# ESP_Breakout.net
KiCad netlist of a schematic drawn in EAGLE
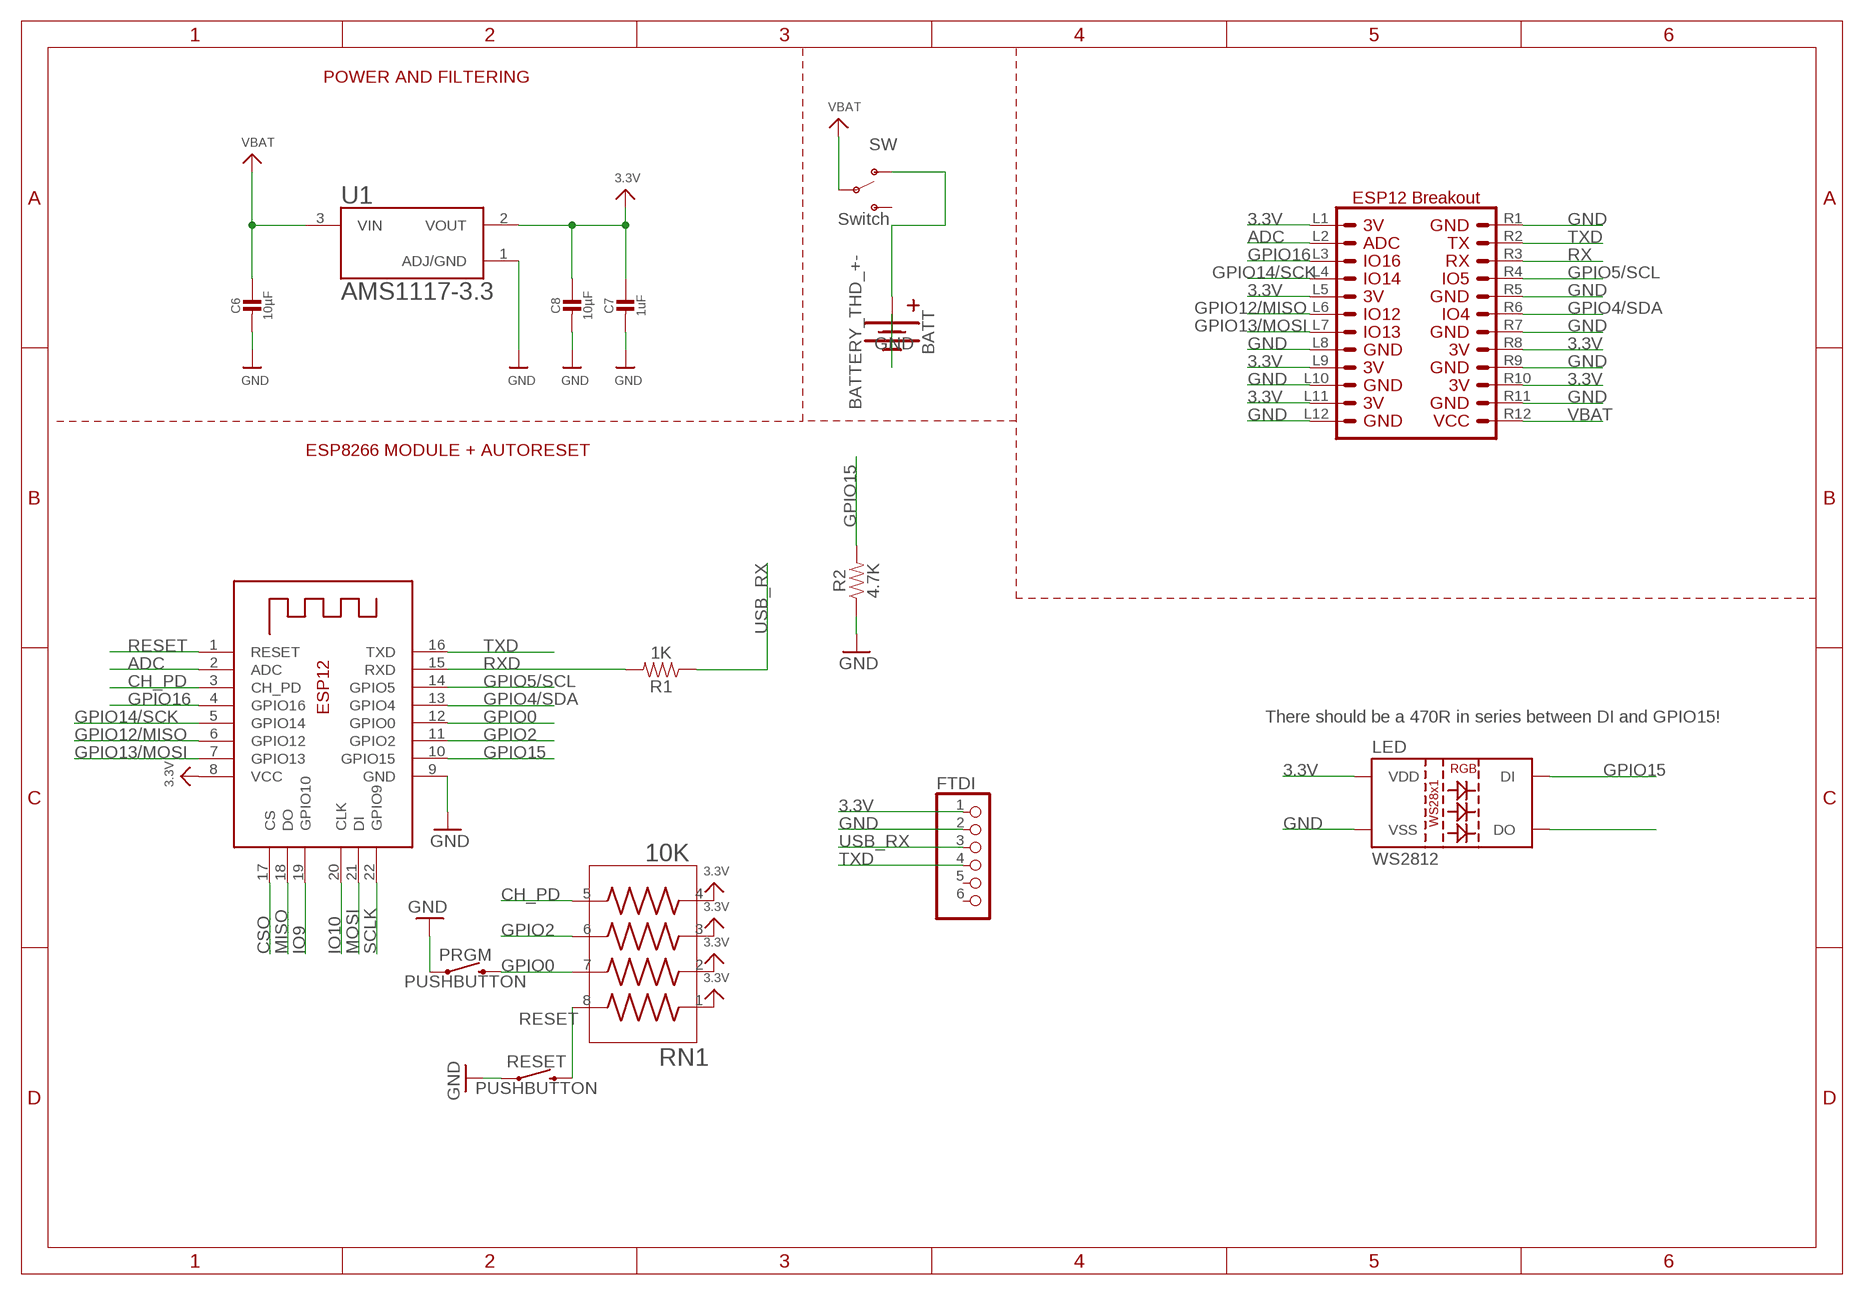
[diagram p0: schematic, sheet 1]

(export (version "E")
  (design (tool "Eeschema 10.0.6"))
  (components
    (comp (ref "BATT")
      (value "BATTERY_THD_+-")
      (footprint "eagle-import:1X02_PLUS_MINUS")
      (libsource (lib "eagle-import") (part "BATTERY_THD_+-"))
    )
    (comp (ref "C6")
      (value "10µF")
      (footprint "eagle-import:MICROBUILDER__0805")
      (libsource (lib "eagle-import") (part "MICROBUILDER_CAP_CERAMIC_0805"))
    )
    (comp (ref "C7")
      (value "1uF")
      (footprint "eagle-import:MICROBUILDER__0603")
      (libsource (lib "eagle-import") (part "MICROBUILDER_CAP_CERAMIC_0603"))
    )
    (comp (ref "C8")
      (value "10µF")
      (footprint "eagle-import:MICROBUILDER__0805")
      (libsource (lib "eagle-import") (part "MICROBUILDER_CAP_CERAMIC_0805"))
    )
    (comp (ref "FTDI")
      (value "PINHD-1X6")
      (footprint "eagle-import:1X06")
      (libsource (lib "eagle-import") (part "PINHD-1X6"))
    )
    (comp (ref "LED")
      (value "WS2812")
      (footprint "eagle-import:LED-TRICOLOR-5050-IC")
      (libsource (lib "eagle-import") (part "WS2812"))
    )
    (comp (ref "PRGM")
      (value "PUSHBUTTON")
      (footprint "eagle-import:TACTILE_SWITCH_SMD_6.0X3.5MM")
      (libsource (lib "eagle-import") (part "PUSHBUTTON"))
    )
    (comp (ref "R1")
      (value "1K")
      (footprint "eagle-import:1206")
      (libsource (lib "eagle-import") (part "RESISTOR1206"))
    )
    (comp (ref "R2")
      (value "4.7K")
      (footprint "eagle-import:1206")
      (libsource (lib "eagle-import") (part "RESISTOR1206"))
    )
    (comp (ref "RESET")
      (value "PUSHBUTTON")
      (footprint "eagle-import:TACTILE_SWITCH_SMD_6.0X3.5MM")
      (libsource (lib "eagle-import") (part "PUSHBUTTON"))
    )
    (comp (ref "RN1")
      (value "10K")
      (footprint "eagle-import:RESCAF80P320X160X60-8N")
      (fields (field (name "MF") "Bourns") (field (name "MP") "CAY16-750J4LF"))
      (libsource (lib "eagle-import") (part "RESISTOR_ARRAY_1206"))
    )
    (comp (ref "SW")
      (value "Switch")
      (footprint "eagle-import:SWITCH_SPDT_PTH_11.6X4.0MM")
      (libsource (lib "eagle-import") (part "SWITCH_SPDT_SLIDE"))
    )
    (comp (ref "U$7")
      (value "ESP12_BREAKOUT")
      (footprint "eagle-import:ESP12_BREAKOUT_CONN")
      (libsource (lib "eagle-import") (part "ESP12_BREAKOUT"))
    )
    (comp (ref "U1")
      (value "AMS1117-3.3")
      (footprint "eagle-import:SOT229P700X180-4N")
      (fields (field (name "MF") "Advanced Monolithic Systems"))
      (libsource (lib "eagle-import") (part "AMS1117-3.3"))
    )
    (comp (ref "X2")
      (value "ESP-12")
      (footprint "eagle-import:ESP-12E")
      (libsource (lib "eagle-import") (part "ESP-12E"))
    )
  )
  (nets
    (net (code "1") (name "/ADC") (class "Default")
      (node (ref "U$7") (pin "L2") (pinfunction "L2_L2") (pintype "passive"))
      (node (ref "X2") (pin "2") (pinfunction "ADC_2") (pintype "passive"))
    )
    (net (code "2") (name "/CH_PD") (class "Default")
      (node (ref "RN1") (pin "5") (pinfunction "5_5") (pintype "passive"))
      (node (ref "X2") (pin "3") (pinfunction "CH_PD_3") (pintype "input"))
    )
    (net (code "3") (name "/CSO") (class "Default")
      (node (ref "X2") (pin "17") (pinfunction "CS_17") (pintype "bidirectional"))
    )
    (net (code "4") (name "/GPIO0") (class "Default")
      (node (ref "PRGM") (pin "2") (pinfunction "2_2") (pintype "passive"))
      (node (ref "RN1") (pin "7") (pinfunction "7_7") (pintype "passive"))
      (node (ref "X2") (pin "12") (pinfunction "GPIO0_12") (pintype "bidirectional"))
    )
    (net (code "5") (name "/GPIO2") (class "Default")
      (node (ref "RN1") (pin "6") (pinfunction "6_6") (pintype "passive"))
      (node (ref "X2") (pin "11") (pinfunction "GPIO2_11") (pintype "bidirectional"))
    )
    (net (code "6") (name "/GPIO4{slash}SDA") (class "Default")
      (node (ref "U$7") (pin "R6") (pinfunction "R6_R6") (pintype "passive"))
      (node (ref "X2") (pin "13") (pinfunction "GPIO4_13") (pintype "bidirectional"))
    )
    (net (code "7") (name "/GPIO5{slash}SCL") (class "Default")
      (node (ref "U$7") (pin "R4") (pinfunction "R4_R4") (pintype "passive"))
      (node (ref "X2") (pin "14") (pinfunction "GPIO5_14") (pintype "bidirectional"))
    )
    (net (code "8") (name "/GPIO12{slash}MISO") (class "Default")
      (node (ref "U$7") (pin "L6") (pinfunction "L6_L6") (pintype "passive"))
      (node (ref "X2") (pin "6") (pinfunction "GPIO12_6") (pintype "bidirectional"))
    )
    (net (code "9") (name "/GPIO13{slash}MOSI") (class "Default")
      (node (ref "U$7") (pin "L7") (pinfunction "L7_L7") (pintype "passive"))
      (node (ref "X2") (pin "7") (pinfunction "GPIO13_7") (pintype "bidirectional"))
    )
    (net (code "10") (name "/GPIO14{slash}SCK") (class "Default")
      (node (ref "U$7") (pin "L4") (pinfunction "L4_L4") (pintype "passive"))
      (node (ref "X2") (pin "5") (pinfunction "GPIO14_5") (pintype "bidirectional"))
    )
    (net (code "11") (name "/GPIO15") (class "Default")
      (node (ref "LED") (pin "DIN") (pinfunction "DI_DIN") (pintype "bidirectional"))
      (node (ref "R2") (pin "2") (pinfunction "2_2") (pintype "passive"))
      (node (ref "X2") (pin "10") (pinfunction "GPIO15_10") (pintype "bidirectional"))
    )
    (net (code "12") (name "/GPIO16") (class "Default")
      (node (ref "U$7") (pin "L3") (pinfunction "L3_L3") (pintype "passive"))
      (node (ref "X2") (pin "4") (pinfunction "GPIO16_4") (pintype "bidirectional"))
    )
    (net (code "13") (name "/IO9") (class "Default")
      (node (ref "X2") (pin "19") (pinfunction "GPIO10_19") (pintype "bidirectional"))
    )
    (net (code "14") (name "/IO10") (class "Default")
      (node (ref "X2") (pin "20") (pinfunction "CLK_20") (pintype "bidirectional"))
    )
    (net (code "15") (name "/MISO") (class "Default")
      (node (ref "X2") (pin "18") (pinfunction "DO_18") (pintype "bidirectional"))
    )
    (net (code "16") (name "/MOSI") (class "Default")
      (node (ref "X2") (pin "21") (pinfunction "DI_21") (pintype "bidirectional"))
    )
    (net (code "17") (name "/RESET") (class "Default")
      (node (ref "RESET") (pin "2") (pinfunction "2_2") (pintype "passive"))
      (node (ref "RN1") (pin "8") (pinfunction "8_8") (pintype "passive"))
      (node (ref "X2") (pin "1") (pinfunction "RESET_1") (pintype "input"))
    )
    (net (code "18") (name "/RX") (class "Default")
      (node (ref "U$7") (pin "R3") (pinfunction "R3_R3") (pintype "passive"))
    )
    (net (code "19") (name "/RXD") (class "Default")
      (node (ref "R1") (pin "2") (pinfunction "2_2") (pintype "passive"))
      (node (ref "X2") (pin "15") (pinfunction "RXD_15") (pintype "input"))
    )
    (net (code "20") (name "/SCLK") (class "Default")
      (node (ref "X2") (pin "22") (pinfunction "GPIO9_22") (pintype "bidirectional"))
    )
    (net (code "21") (name "/TXD") (class "Default")
      (node (ref "FTDI") (pin "4") (pinfunction "4_4") (pintype "passive"))
      (node (ref "U$7") (pin "R2") (pinfunction "R2_R2") (pintype "passive"))
      (node (ref "X2") (pin "16") (pinfunction "TXD_16") (pintype "output"))
    )
    (net (code "22") (name "/USB_RX") (class "Default")
      (node (ref "FTDI") (pin "3") (pinfunction "3_3") (pintype "passive"))
      (node (ref "R1") (pin "1") (pinfunction "1_1") (pintype "passive"))
    )
    (net (code "23") (name "3.3V") (class "Default")
      (node (ref "C7") (pin "1") (pinfunction "1_1") (pintype "passive"))
      (node (ref "C8") (pin "1") (pinfunction "1_1") (pintype "passive"))
      (node (ref "FTDI") (pin "1") (pinfunction "1_1") (pintype "passive"))
      (node (ref "LED") (pin "VDD") (pinfunction "VDD_VDD") (pintype "bidirectional"))
      (node (ref "RN1") (pin "1") (pinfunction "1_1") (pintype "passive"))
      (node (ref "RN1") (pin "2") (pinfunction "2_2") (pintype "passive"))
      (node (ref "RN1") (pin "3") (pinfunction "3_3") (pintype "passive"))
      (node (ref "RN1") (pin "4") (pinfunction "4_4") (pintype "passive"))
      (node (ref "U$7") (pin "L1") (pinfunction "L1_L1") (pintype "passive"))
      (node (ref "U$7") (pin "L11") (pinfunction "L11_L11") (pintype "passive"))
      (node (ref "U$7") (pin "L5") (pinfunction "L5_L5") (pintype "passive"))
      (node (ref "U$7") (pin "L9") (pinfunction "L9_L9") (pintype "passive"))
      (node (ref "U$7") (pin "R10") (pinfunction "R10_R10") (pintype "passive"))
      (node (ref "U$7") (pin "R8") (pinfunction "R8_R8") (pintype "passive"))
      (node (ref "U1") (pin "2") (pinfunction "VOUT_2") (pintype "output"))
      (node (ref "X2") (pin "8") (pinfunction "VCC_8") (pintype "power_in"))
    )
    (net (code "24") (name "GND") (class "Default")
      (node (ref "BATT") (pin "-") (pinfunction "-_-") (pintype "power_in"))
      (node (ref "C6") (pin "2") (pinfunction "2_2") (pintype "passive"))
      (node (ref "C7") (pin "2") (pinfunction "2_2") (pintype "passive"))
      (node (ref "C8") (pin "2") (pinfunction "2_2") (pintype "passive"))
      (node (ref "FTDI") (pin "2") (pinfunction "2_2") (pintype "passive"))
      (node (ref "LED") (pin "VSS") (pinfunction "VSS_VSS") (pintype "bidirectional"))
      (node (ref "PRGM") (pin "1") (pinfunction "1_1") (pintype "passive"))
      (node (ref "R2") (pin "1") (pinfunction "1_1") (pintype "passive"))
      (node (ref "RESET") (pin "1") (pinfunction "1_1") (pintype "passive"))
      (node (ref "U$7") (pin "L10") (pinfunction "L10_L10") (pintype "passive"))
      (node (ref "U$7") (pin "L12") (pinfunction "L12_L12") (pintype "passive"))
      (node (ref "U$7") (pin "L8") (pinfunction "L8_L8") (pintype "passive"))
      (node (ref "U$7") (pin "R1") (pinfunction "R1_R1") (pintype "passive"))
      (node (ref "U$7") (pin "R11") (pinfunction "R11_R11") (pintype "passive"))
      (node (ref "U$7") (pin "R5") (pinfunction "R5_R5") (pintype "passive"))
      (node (ref "U$7") (pin "R7") (pinfunction "R7_R7") (pintype "passive"))
      (node (ref "U$7") (pin "R9") (pinfunction "R9_R9") (pintype "passive"))
      (node (ref "U1") (pin "1") (pinfunction "ADJ/GND_1") (pintype "power_in"))
      (node (ref "X2") (pin "9") (pinfunction "GND_9") (pintype "power_in"))
    )
    (net (code "25") (name "Net-(SW-O)") (class "Default")
      (node (ref "BATT") (pin "+") (pinfunction "+_+") (pintype "power_in"))
      (node (ref "SW") (pin "1") (pinfunction "O_1") (pintype "passive"))
    )
    (net (code "26") (name "VBAT") (class "Default")
      (node (ref "C6") (pin "1") (pinfunction "1_1") (pintype "passive"))
      (node (ref "SW") (pin "2") (pinfunction "P_2") (pintype "passive"))
      (node (ref "U$7") (pin "R12") (pinfunction "R12_R12") (pintype "passive"))
      (node (ref "U1") (pin "3") (pinfunction "VIN_3") (pintype "input"))
    )
    (net (code "27") (name "unconnected-(FTDI-Pad5)") (class "Default")
      (node (ref "FTDI") (pin "5") (pinfunction "5_5") (pintype "passive"))
    )
    (net (code "28") (name "unconnected-(FTDI-Pad6)") (class "Default")
      (node (ref "FTDI") (pin "6") (pinfunction "6_6") (pintype "passive"))
    )
    (net (code "29") (name "unconnected-(LED-DO-PadDOUT)") (class "Default")
      (node (ref "LED") (pin "DOUT") (pinfunction "DO_DOUT") (pintype "bidirectional"))
    )
    (net (code "30") (name "unconnected-(SW-S-Pad3)") (class "Default")
      (node (ref "SW") (pin "3") (pinfunction "S_3") (pintype "passive"))
    )
  )
)
